# cytron-1.net
KiCad netlist of a schematic drawn in EAGLE
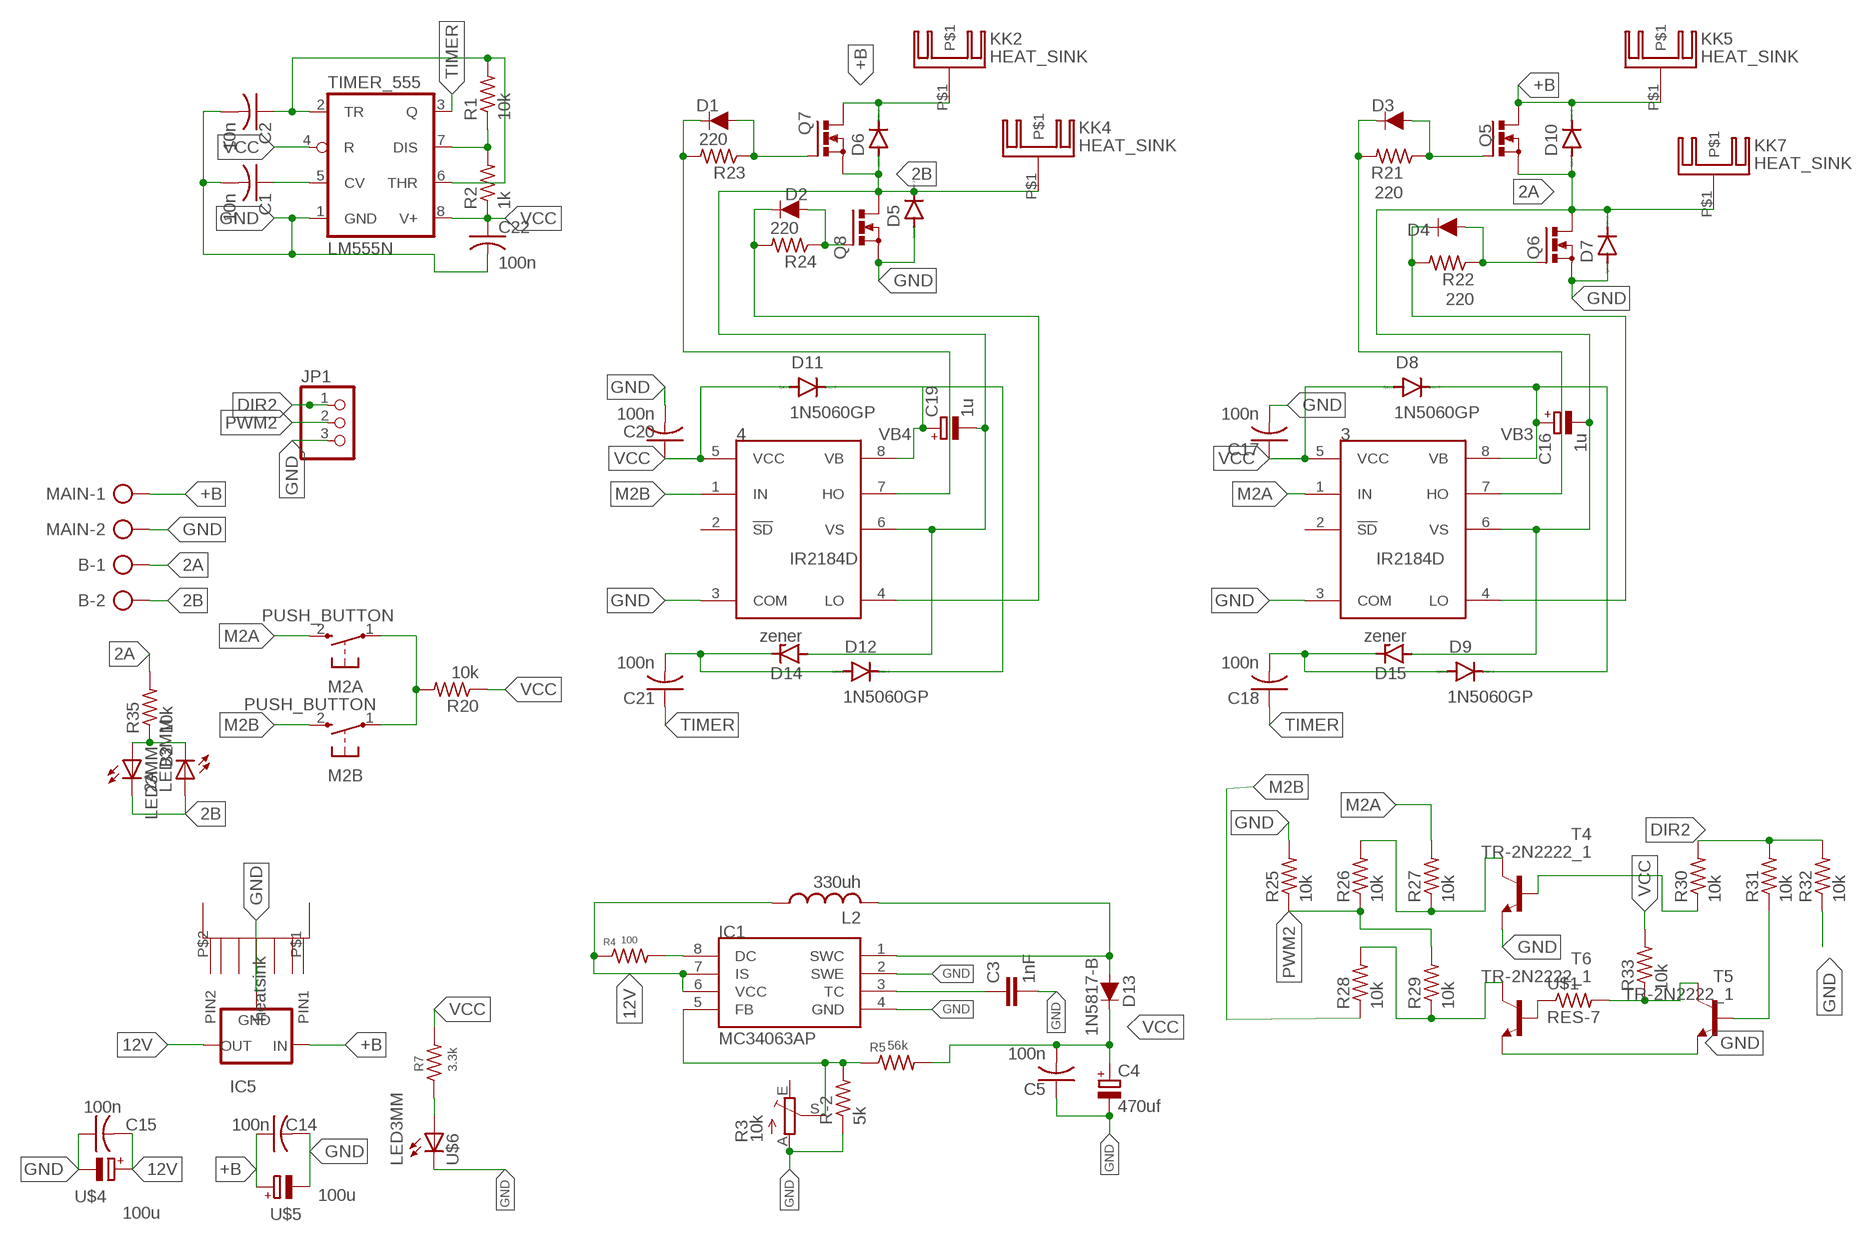
[diagram p0: schematic, sheet 1]

(export (version "E")
  (design (tool "Eeschema 10.0.6"))
  (components
    (comp (ref "2A")
      (value "LED3MM")
      (footprint "eagle-import:LED3MM")
      (libsource (lib "eagle-import") (part "LED3MM"))
    )
    (comp (ref "3")
      (value "IR2184D")
      (footprint "eagle-import:DIL08")
      (libsource (lib "eagle-import") (part "IR2184D"))
    )
    (comp (ref "4")
      (value "IR2184D")
      (footprint "eagle-import:DIL08")
      (libsource (lib "eagle-import") (part "IR2184D"))
    )
    (comp (ref "B")
      (value "ROSTA.POWER")
      (footprint "eagle-import:W239-302")
      (libsource (lib "eagle-import") (part "ROSTA.POWER"))
    )
    (comp (ref "B2")
      (value "LED3MM")
      (footprint "eagle-import:LED3MM")
      (libsource (lib "eagle-import") (part "LED3MM"))
    )
    (comp (ref "C1")
      (value "10n")
      (footprint "eagle-import:C025-025X050")
      (libsource (lib "eagle-import") (part "C-US025-025X050"))
    )
    (comp (ref "C2")
      (value "10n")
      (footprint "eagle-import:C025-025X050")
      (libsource (lib "eagle-import") (part "C-US025-025X050"))
    )
    (comp (ref "C3")
      (value "1nF")
      (footprint "eagle-import:C025-025X050")
      (fields (field (name "SPICEPREFIX") "C"))
      (libsource (lib "eagle-import") (part "CAPACITOR"))
    )
    (comp (ref "C4")
      (value "470uf")
      (footprint "eagle-import:E3,5-8")
      (fields (field (name "SPICEPREFIX") "C"))
      (libsource (lib "eagle-import") (part "CAP_POL"))
    )
    (comp (ref "C5")
      (value "100n")
      (footprint "eagle-import:C025-025X050")
      (libsource (lib "eagle-import") (part "C-US025-025X050"))
    )
    (comp (ref "C14")
      (value "100n")
      (footprint "eagle-import:C025-025X050")
      (libsource (lib "eagle-import") (part "C-US025-025X050"))
    )
    (comp (ref "C15")
      (value "100n")
      (footprint "eagle-import:C025-025X050")
      (libsource (lib "eagle-import") (part "C-US025-025X050"))
    )
    (comp (ref "C16")
      (value "1u")
      (footprint "eagle-import:E5-5")
      (libsource (lib "eagle-import") (part "CPOL-EUE5-5"))
    )
    (comp (ref "C17")
      (value "100n")
      (footprint "eagle-import:C025-025X050")
      (libsource (lib "eagle-import") (part "C-US025-025X050"))
    )
    (comp (ref "C18")
      (value "100n")
      (footprint "eagle-import:C025-025X050")
      (libsource (lib "eagle-import") (part "C-US025-025X050"))
    )
    (comp (ref "C19")
      (value "1u")
      (footprint "eagle-import:E5-5")
      (libsource (lib "eagle-import") (part "CPOL-EUE5-5"))
    )
    (comp (ref "C20")
      (value "100n")
      (footprint "eagle-import:C025-025X050")
      (libsource (lib "eagle-import") (part "C-US025-025X050"))
    )
    (comp (ref "C21")
      (value "100n")
      (footprint "eagle-import:C025-025X050")
      (libsource (lib "eagle-import") (part "C-US025-025X050"))
    )
    (comp (ref "C22")
      (value "100n")
      (footprint "eagle-import:C025-025X050")
      (libsource (lib "eagle-import") (part "C-US025-025X050"))
    )
    (comp (ref "D1")
      (value "1A/50V/1.1V")
      (footprint "eagle-import:DIODE-1N4001")
      (libsource (lib "eagle-import") (part "DIODE(1A)-PTH"))
    )
    (comp (ref "D2")
      (value "1A/50V/1.1V")
      (footprint "eagle-import:DIODE-1N4001")
      (libsource (lib "eagle-import") (part "DIODE(1A)-PTH"))
    )
    (comp (ref "D3")
      (value "1A/50V/1.1V")
      (footprint "eagle-import:DIODE-1N4001")
      (libsource (lib "eagle-import") (part "DIODE(1A)-PTH"))
    )
    (comp (ref "D4")
      (value "1A/50V/1.1V")
      (footprint "eagle-import:DIODE-1N4001")
      (libsource (lib "eagle-import") (part "DIODE(1A)-PTH"))
    )
    (comp (ref "D5")
      (value "BY396")
      (footprint "eagle-import:DO201-15")
      (libsource (lib "eagle-import") (part "BY396"))
    )
    (comp (ref "D6")
      (value "BY396")
      (footprint "eagle-import:DO201-15")
      (libsource (lib "eagle-import") (part "BY396"))
    )
    (comp (ref "D7")
      (value "BY396")
      (footprint "eagle-import:DO201-15")
      (libsource (lib "eagle-import") (part "BY396"))
    )
    (comp (ref "D8")
      (value "1N5060GP")
      (footprint "eagle-import:DO15-12")
      (libsource (lib "eagle-import") (part "1N5060GP"))
    )
    (comp (ref "D9")
      (value "1N5060GP")
      (footprint "eagle-import:DO15-12")
      (libsource (lib "eagle-import") (part "1N5060GP"))
    )
    (comp (ref "D10")
      (value "BY396")
      (footprint "eagle-import:DO201-15")
      (libsource (lib "eagle-import") (part "BY396"))
    )
    (comp (ref "D11")
      (value "1N5060GP")
      (footprint "eagle-import:DO15-12")
      (libsource (lib "eagle-import") (part "1N5060GP"))
    )
    (comp (ref "D12")
      (value "1N5060GP")
      (footprint "eagle-import:DO15-12")
      (libsource (lib "eagle-import") (part "1N5060GP"))
    )
    (comp (ref "D13")
      (value "1N5817-B")
      (footprint "eagle-import:DIODE-1N4001")
      (fields (field (name "SPICEPREFIX") "D"))
      (libsource (lib "eagle-import") (part "DIODE(1A)-PTH"))
    )
    (comp (ref "D14")
      (value "zener")
      (footprint "eagle-import:SOD81")
      (libsource (lib "eagle-import") (part "BZD23"))
    )
    (comp (ref "D15")
      (value "zener")
      (footprint "eagle-import:SOD81")
      (libsource (lib "eagle-import") (part "BZD23"))
    )
    (comp (ref "IC1")
      (value "MC34063AP")
      (footprint "eagle-import:DIL08")
      (fields (field (name "SPICEPREFIX") "X"))
      (libsource (lib "eagle-import") (part "MC34063AP"))
    )
    (comp (ref "IC5")
      (value "78XXS")
      (footprint "eagle-import:78XXS")
      (libsource (lib "eagle-import") (part "78XXS"))
    )
    (comp (ref "JP1")
      (value "PINHD-3_DATA")
      (footprint "eagle-import:1X03_DATA")
      (libsource (lib "eagle-import") (part "PINHD-3_DATA"))
    )
    (comp (ref "KK2")
      (value "HEAT_SINK")
      (footprint "eagle-import:SK95-2M3")
      (libsource (lib "eagle-import") (part "HEAT_SINK"))
    )
    (comp (ref "KK4")
      (value "HEAT_SINK")
      (footprint "eagle-import:SK95-2M3")
      (libsource (lib "eagle-import") (part "HEAT_SINK"))
    )
    (comp (ref "KK5")
      (value "HEAT_SINK")
      (footprint "eagle-import:SK95-2M3")
      (libsource (lib "eagle-import") (part "HEAT_SINK"))
    )
    (comp (ref "KK7")
      (value "HEAT_SINK")
      (footprint "eagle-import:SK95-2M3")
      (libsource (lib "eagle-import") (part "HEAT_SINK"))
    )
    (comp (ref "L2")
      (value "330uh")
      (footprint "eagle-import:POWER-CHOKE_WE-TPC")
      (libsource (lib "eagle-import") (part "L-USWE-TPC"))
    )
    (comp (ref "M2A")
      (value "PUSH_BUTTON")
      (footprint "eagle-import:B3F-10XX")
      (libsource (lib "eagle-import") (part "PUSH_BUTTON"))
    )
    (comp (ref "M2B")
      (value "PUSH_BUTTON")
      (footprint "eagle-import:B3F-10XX")
      (libsource (lib "eagle-import") (part "PUSH_BUTTON"))
    )
    (comp (ref "MAIN")
      (value "ROSTA.POWER")
      (footprint "eagle-import:W239-302")
      (libsource (lib "eagle-import") (part "ROSTA.POWER"))
    )
    (comp (ref "Q5")
      (value "MOSFET_NTO220BV")
      (footprint "eagle-import:TO220BV")
      (libsource (lib "eagle-import") (part "MOSFET_NTO220BV"))
    )
    (comp (ref "Q6")
      (value "MOSFET_NTO220BV")
      (footprint "eagle-import:TO220BV")
      (libsource (lib "eagle-import") (part "MOSFET_NTO220BV"))
    )
    (comp (ref "Q7")
      (value "MOSFET_NTO220BV")
      (footprint "eagle-import:TO220BV")
      (libsource (lib "eagle-import") (part "MOSFET_NTO220BV"))
    )
    (comp (ref "Q8")
      (value "MOSFET_NTO220BV")
      (footprint "eagle-import:TO220BV")
      (libsource (lib "eagle-import") (part "MOSFET_NTO220BV"))
    )
    (comp (ref "R-2")
      (value "5k")
      (footprint "eagle-import:0204_7")
      (libsource (lib "eagle-import") (part "RES-7"))
    )
    (comp (ref "R1")
      (value "10k")
      (footprint "eagle-import:0204_7")
      (libsource (lib "eagle-import") (part "R-US_0204/7"))
    )
    (comp (ref "R2")
      (value "1k")
      (footprint "eagle-import:0204_7")
      (libsource (lib "eagle-import") (part "R-US_0204/7"))
    )
    (comp (ref "R3")
      (value "10k")
      (footprint "eagle-import:CA6V")
      (fields (field (name "SPICEPREFIX") "J"))
      (libsource (lib "eagle-import") (part "TRIM_EU-CA6V"))
    )
    (comp (ref "R4")
      (value "100")
      (footprint "eagle-import:0204_7")
      (fields (field (name "SPICEPREFIX") "R"))
      (libsource (lib "eagle-import") (part "RES-7"))
    )
    (comp (ref "R5")
      (value "56k")
      (footprint "eagle-import:0204_7")
      (fields (field (name "SPICEPREFIX") "R"))
      (libsource (lib "eagle-import") (part "RES-7"))
    )
    (comp (ref "R7")
      (value "3.3k")
      (footprint "eagle-import:0204_7")
      (fields (field (name "SPICEPREFIX") "R"))
      (libsource (lib "eagle-import") (part "RES-7"))
    )
    (comp (ref "R20")
      (value "10k")
      (footprint "eagle-import:0204_7")
      (libsource (lib "eagle-import") (part "R-US_0204/7"))
    )
    (comp (ref "R21")
      (value "220")
      (footprint "eagle-import:0204_7")
      (libsource (lib "eagle-import") (part "R-US_0204/7"))
    )
    (comp (ref "R22")
      (value "220")
      (footprint "eagle-import:0204_7")
      (libsource (lib "eagle-import") (part "R-US_0204/7"))
    )
    (comp (ref "R23")
      (value "220")
      (footprint "eagle-import:0204_7")
      (libsource (lib "eagle-import") (part "R-US_0204/7"))
    )
    (comp (ref "R24")
      (value "220")
      (footprint "eagle-import:0204_7")
      (libsource (lib "eagle-import") (part "R-US_0204/7"))
    )
    (comp (ref "R25")
      (value "10k")
      (footprint "eagle-import:0204_7")
      (libsource (lib "eagle-import") (part "R-US_0204/7"))
    )
    (comp (ref "R26")
      (value "10k")
      (footprint "eagle-import:0204_7")
      (libsource (lib "eagle-import") (part "R-US_0204/7"))
    )
    (comp (ref "R27")
      (value "10k")
      (footprint "eagle-import:0204_7")
      (libsource (lib "eagle-import") (part "R-US_0204/7"))
    )
    (comp (ref "R28")
      (value "10k")
      (footprint "eagle-import:0204_7")
      (libsource (lib "eagle-import") (part "R-US_0204/7"))
    )
    (comp (ref "R29")
      (value "10k")
      (footprint "eagle-import:0204_7")
      (libsource (lib "eagle-import") (part "R-US_0204/7"))
    )
    (comp (ref "R30")
      (value "10k")
      (footprint "eagle-import:0204_7")
      (libsource (lib "eagle-import") (part "R-US_0204/7"))
    )
    (comp (ref "R31")
      (value "10k")
      (footprint "eagle-import:0204_7")
      (libsource (lib "eagle-import") (part "R-US_0204/7"))
    )
    (comp (ref "R32")
      (value "10k")
      (footprint "eagle-import:0204_7")
      (libsource (lib "eagle-import") (part "R-US_0204/7"))
    )
    (comp (ref "R33")
      (value "10k")
      (footprint "eagle-import:0204_7")
      (libsource (lib "eagle-import") (part "R-US_0204/7"))
    )
    (comp (ref "R35")
      (value "10k")
      (footprint "eagle-import:0204_7")
      (libsource (lib "eagle-import") (part "R-US_0204/7"))
    )
    (comp (ref "T4")
      (value "TR-2N2222_1")
      (footprint "eagle-import:TO92-EBC")
      (fields (field (name "SPICEPREFIX") "J"))
      (libsource (lib "eagle-import") (part "TR-2N2222_1"))
    )
    (comp (ref "T5")
      (value "TR-2N2222_1")
      (footprint "eagle-import:TO92-EBC")
      (fields (field (name "SPICEPREFIX") "J"))
      (libsource (lib "eagle-import") (part "TR-2N2222_1"))
    )
    (comp (ref "T6")
      (value "TR-2N2222_1")
      (footprint "eagle-import:TO92-EBC")
      (fields (field (name "SPICEPREFIX") "J"))
      (libsource (lib "eagle-import") (part "TR-2N2222_1"))
    )
    (comp (ref "TIMER_555")
      (value "LM555N")
      (footprint "eagle-import:DIL08")
      (libsource (lib "eagle-import") (part "555NLM"))
    )
    (comp (ref "U$1")
      (value "RES-7")
      (footprint "eagle-import:0204_7")
      (fields (field (name "SPICEPREFIX") "B"))
      (libsource (lib "eagle-import") (part "RES-7"))
    )
    (comp (ref "U$3")
      (value "HEAT-SINK")
      (footprint "eagle-import:HEAT_SINK")
      (libsource (lib "eagle-import") (part "HEAT-SINK"))
    )
    (comp (ref "U$4")
      (value "100u")
      (footprint "eagle-import:E3,5-8")
      (libsource (lib "eagle-import") (part "CAP_POL"))
    )
    (comp (ref "U$5")
      (value "100u")
      (footprint "eagle-import:E3,5-8")
      (libsource (lib "eagle-import") (part "CAP_POL"))
    )
    (comp (ref "U$6")
      (value "LED3MM")
      (footprint "eagle-import:LED3MM")
      (fields (field (name "SPICEPREFIX") "B"))
      (libsource (lib "eagle-import") (part "LED3MM"))
    )
  )
  (nets
    (net (code "1") (name "+B") (class "Default")
      (node (ref "C14") (pin "1") (pinfunction "1_1") (pintype "passive"))
      (node (ref "D10") (pin "C") (pinfunction "C_C") (pintype "passive"))
      (node (ref "D6") (pin "C") (pinfunction "C_C") (pintype "passive"))
      (node (ref "IC5") (pin "IN") (pinfunction "IN_IN") (pintype "input"))
      (node (ref "KK2") (pin "P$1") (pinfunction "P$1_P$1") (pintype "bidirectional"))
      (node (ref "KK5") (pin "P$1") (pinfunction "P$1_P$1") (pintype "bidirectional"))
      (node (ref "MAIN") (pin "1") (pinfunction "KL_1") (pintype "passive"))
      (node (ref "Q5") (pin "D") (pinfunction "D_D") (pintype "passive"))
      (node (ref "Q7") (pin "D") (pinfunction "D_D") (pintype "passive"))
      (node (ref "U$5") (pin "+") (pinfunction "+_+") (pintype "passive"))
    )
    (net (code "2") (name "/VB3") (class "Default")
      (node (ref "3") (pin "8") (pinfunction "VB_8") (pintype "power_in"))
      (node (ref "C16") (pin "+") (pinfunction "+_+") (pintype "passive"))
      (node (ref "D8") (pin "C") (pinfunction "C_C") (pintype "passive"))
      (node (ref "D9") (pin "C") (pinfunction "C_C") (pintype "passive"))
    )
    (net (code "3") (name "/VB4") (class "Default")
      (node (ref "4") (pin "8") (pinfunction "VB_8") (pintype "power_in"))
      (node (ref "C19") (pin "+") (pinfunction "+_+") (pintype "passive"))
      (node (ref "D11") (pin "C") (pinfunction "C_C") (pintype "passive"))
      (node (ref "D12") (pin "C") (pinfunction "C_C") (pintype "passive"))
    )
    (net (code "4") (name "2A") (class "Default")
      (node (ref "3") (pin "6") (pinfunction "VS_6") (pintype "power_in"))
      (node (ref "B") (pin "1") (pinfunction "KL_1") (pintype "passive"))
      (node (ref "C16") (pin "-") (pinfunction "-_-") (pintype "passive"))
      (node (ref "D10") (pin "A") (pinfunction "A_A") (pintype "passive"))
      (node (ref "D15") (pin "A") (pinfunction "A_A") (pintype "passive"))
      (node (ref "D7") (pin "C") (pinfunction "C_C") (pintype "passive"))
      (node (ref "KK7") (pin "P$1") (pinfunction "P$1_P$1") (pintype "bidirectional"))
      (node (ref "Q5") (pin "S") (pinfunction "S_S") (pintype "passive"))
      (node (ref "Q6") (pin "D") (pinfunction "D_D") (pintype "passive"))
      (node (ref "R35") (pin "2") (pinfunction "2_2") (pintype "passive"))
    )
    (net (code "5") (name "2B") (class "Default")
      (node (ref "2A") (pin "K") (pinfunction "C_K") (pintype "passive"))
      (node (ref "4") (pin "6") (pinfunction "VS_6") (pintype "power_in"))
      (node (ref "B") (pin "2") (pinfunction "KL_2") (pintype "passive"))
      (node (ref "B2") (pin "A") (pinfunction "A_A") (pintype "passive"))
      (node (ref "C19") (pin "-") (pinfunction "-_-") (pintype "passive"))
      (node (ref "D14") (pin "A") (pinfunction "A_A") (pintype "passive"))
      (node (ref "D5") (pin "C") (pinfunction "C_C") (pintype "passive"))
      (node (ref "D6") (pin "A") (pinfunction "A_A") (pintype "passive"))
      (node (ref "KK4") (pin "P$1") (pinfunction "P$1_P$1") (pintype "bidirectional"))
      (node (ref "Q7") (pin "S") (pinfunction "S_S") (pintype "passive"))
      (node (ref "Q8") (pin "D") (pinfunction "D_D") (pintype "passive"))
    )
    (net (code "6") (name "12V") (class "Default")
      (node (ref "C15") (pin "2") (pinfunction "2_2") (pintype "passive"))
      (node (ref "IC1") (pin "6") (pinfunction "VCC_6") (pintype "passive"))
      (node (ref "IC1") (pin "7") (pinfunction "IS_7") (pintype "passive"))
      (node (ref "IC5") (pin "OUT") (pinfunction "OUT_OUT") (pintype "passive"))
      (node (ref "L2") (pin "1") (pinfunction "1_1") (pintype "passive"))
      (node (ref "R4") (pin "1") (pinfunction "1_1") (pintype "passive"))
      (node (ref "U$4") (pin "+") (pinfunction "+_+") (pintype "passive"))
    )
    (net (code "7") (name "DIR2") (class "Default")
      (node (ref "JP1") (pin "1") (pinfunction "1_1") (pintype "passive"))
      (node (ref "R30") (pin "2") (pinfunction "2_2") (pintype "passive"))
      (node (ref "R31") (pin "2") (pinfunction "2_2") (pintype "passive"))
      (node (ref "R32") (pin "2") (pinfunction "2_2") (pintype "passive"))
    )
    (net (code "8") (name "GND") (class "Default")
      (node (ref "3") (pin "3") (pinfunction "COM_3") (pintype "power_in"))
      (node (ref "4") (pin "3") (pinfunction "COM_3") (pintype "power_in"))
      (node (ref "C1") (pin "2") (pinfunction "2_2") (pintype "passive"))
      (node (ref "C14") (pin "2") (pinfunction "2_2") (pintype "passive"))
      (node (ref "C15") (pin "1") (pinfunction "1_1") (pintype "passive"))
      (node (ref "C17") (pin "2") (pinfunction "2_2") (pintype "passive"))
      (node (ref "C2") (pin "2") (pinfunction "2_2") (pintype "passive"))
      (node (ref "C20") (pin "2") (pinfunction "2_2") (pintype "passive"))
      (node (ref "C22") (pin "2") (pinfunction "2_2") (pintype "passive"))
      (node (ref "C3") (pin "2") (pinfunction "2_2") (pintype "passive"))
      (node (ref "C4") (pin "-") (pinfunction "-_-") (pintype "passive"))
      (node (ref "C5") (pin "1") (pinfunction "1_1") (pintype "passive"))
      (node (ref "D5") (pin "A") (pinfunction "A_A") (pintype "passive"))
      (node (ref "D7") (pin "A") (pinfunction "A_A") (pintype "passive"))
      (node (ref "IC1") (pin "2") (pinfunction "SWE_2") (pintype "passive"))
      (node (ref "IC1") (pin "4") (pinfunction "GND_4") (pintype "passive"))
      (node (ref "IC5") (pin "GND") (pinfunction "GND_GND") (pintype "input"))
      (node (ref "JP1") (pin "3") (pinfunction "3_3") (pintype "passive"))
      (node (ref "MAIN") (pin "2") (pinfunction "KL_2") (pintype "passive"))
      (node (ref "Q6") (pin "S") (pinfunction "S_S") (pintype "passive"))
      (node (ref "Q8") (pin "S") (pinfunction "S_S") (pintype "passive"))
      (node (ref "R-2") (pin "1") (pinfunction "1_1") (pintype "passive"))
      (node (ref "R25") (pin "2") (pinfunction "2_2") (pintype "passive"))
      (node (ref "R3") (pin "A") (pinfunction "A_A") (pintype "passive"))
      (node (ref "R32") (pin "1") (pinfunction "1_1") (pintype "passive"))
      (node (ref "T4") (pin "E") (pinfunction "E_E") (pintype "passive"))
      (node (ref "T5") (pin "E") (pinfunction "E_E") (pintype "passive"))
      (node (ref "T6") (pin "E") (pinfunction "E_E") (pintype "passive"))
      (node (ref "TIMER_555") (pin "1") (pinfunction "GND_1") (pintype "power_in"))
      (node (ref "U$4") (pin "-") (pinfunction "-_-") (pintype "passive"))
      (node (ref "U$5") (pin "-") (pinfunction "-_-") (pintype "passive"))
      (node (ref "U$6") (pin "K") (pinfunction "C_K") (pintype "passive"))
    )
    (net (code "9") (name "M2A") (class "Default")
      (node (ref "3") (pin "1") (pinfunction "IN_1") (pintype "input"))
      (node (ref "M2A") (pin "2") (pinfunction "S_2") (pintype "passive"))
      (node (ref "R27") (pin "2") (pinfunction "2_2") (pintype "passive"))
    )
    (net (code "10") (name "M2B") (class "Default")
      (node (ref "4") (pin "1") (pinfunction "IN_1") (pintype "input"))
      (node (ref "M2B") (pin "2") (pinfunction "S_2") (pintype "passive"))
      (node (ref "R28") (pin "1") (pinfunction "1_1") (pintype "passive"))
    )
    (net (code "11") (name "Net-(3-HO)") (class "Default")
      (node (ref "3") (pin "7") (pinfunction "HO_7") (pintype "output"))
      (node (ref "D3") (pin "C") (pinfunction "C_C") (pintype "passive"))
      (node (ref "R21") (pin "2") (pinfunction "2_2") (pintype "passive"))
    )
    (net (code "12") (name "Net-(3-LO)") (class "Default")
      (node (ref "3") (pin "4") (pinfunction "LO_4") (pintype "output"))
      (node (ref "D4") (pin "C") (pinfunction "C_C") (pintype "passive"))
      (node (ref "R22") (pin "2") (pinfunction "2_2") (pintype "passive"))
    )
    (net (code "13") (name "Net-(4-HO)") (class "Default")
      (node (ref "4") (pin "7") (pinfunction "HO_7") (pintype "output"))
      (node (ref "D1") (pin "C") (pinfunction "C_C") (pintype "passive"))
      (node (ref "R23") (pin "2") (pinfunction "2_2") (pintype "passive"))
    )
    (net (code "14") (name "Net-(4-LO)") (class "Default")
      (node (ref "4") (pin "4") (pinfunction "LO_4") (pintype "output"))
      (node (ref "D2") (pin "C") (pinfunction "C_C") (pintype "passive"))
      (node (ref "R24") (pin "2") (pinfunction "2_2") (pintype "passive"))
    )
    (net (code "15") (name "Net-(B2-C)") (class "Default")
      (node (ref "2A") (pin "A") (pinfunction "A_A") (pintype "passive"))
      (node (ref "B2") (pin "K") (pinfunction "C_K") (pintype "passive"))
      (node (ref "R35") (pin "1") (pinfunction "1_1") (pintype "passive"))
    )
    (net (code "16") (name "Net-(C18-Pad2)") (class "Default")
      (node (ref "C18") (pin "2") (pinfunction "2_2") (pintype "passive"))
      (node (ref "D15") (pin "C") (pinfunction "C_C") (pintype "passive"))
      (node (ref "D9") (pin "A") (pinfunction "A_A") (pintype "passive"))
    )
    (net (code "17") (name "Net-(C21-Pad2)") (class "Default")
      (node (ref "C21") (pin "2") (pinfunction "2_2") (pintype "passive"))
      (node (ref "D12") (pin "A") (pinfunction "A_A") (pintype "passive"))
      (node (ref "D14") (pin "C") (pinfunction "C_C") (pintype "passive"))
    )
    (net (code "18") (name "Net-(D1-PadA)") (class "Default")
      (node (ref "D1") (pin "A") (pinfunction "A_A") (pintype "passive"))
      (node (ref "Q7") (pin "G") (pinfunction "G_G") (pintype "passive"))
      (node (ref "R23") (pin "1") (pinfunction "1_1") (pintype "passive"))
    )
    (net (code "19") (name "Net-(D2-PadA)") (class "Default")
      (node (ref "D2") (pin "A") (pinfunction "A_A") (pintype "passive"))
      (node (ref "Q8") (pin "G") (pinfunction "G_G") (pintype "passive"))
      (node (ref "R24") (pin "1") (pinfunction "1_1") (pintype "passive"))
    )
    (net (code "20") (name "Net-(D3-PadA)") (class "Default")
      (node (ref "D3") (pin "A") (pinfunction "A_A") (pintype "passive"))
      (node (ref "Q5") (pin "G") (pinfunction "G_G") (pintype "passive"))
      (node (ref "R21") (pin "1") (pinfunction "1_1") (pintype "passive"))
    )
    (net (code "21") (name "Net-(D4-PadA)") (class "Default")
      (node (ref "D4") (pin "A") (pinfunction "A_A") (pintype "passive"))
      (node (ref "Q6") (pin "G") (pinfunction "G_G") (pintype "passive"))
      (node (ref "R22") (pin "1") (pinfunction "1_1") (pintype "passive"))
    )
    (net (code "22") (name "Net-(IC1-DC)") (class "Default")
      (node (ref "IC1") (pin "8") (pinfunction "DC_8") (pintype "passive"))
      (node (ref "R4") (pin "2") (pinfunction "2_2") (pintype "passive"))
    )
    (net (code "23") (name "Net-(IC1-FB)") (class "Default")
      (node (ref "IC1") (pin "5") (pinfunction "FB_5") (pintype "passive"))
      (node (ref "R-2") (pin "2") (pinfunction "2_2") (pintype "passive"))
      (node (ref "R3") (pin "S") (pinfunction "S_S") (pintype "passive"))
      (node (ref "R5") (pin "1") (pinfunction "1_1") (pintype "passive"))
    )
    (net (code "24") (name "Net-(IC1-SWC)") (class "Default")
      (node (ref "D13") (pin "A") (pinfunction "A_A") (pintype "passive"))
      (node (ref "IC1") (pin "1") (pinfunction "SWC_1") (pintype "passive"))
      (node (ref "L2") (pin "2") (pinfunction "2_2") (pintype "passive"))
    )
    (net (code "25") (name "Net-(IC1-TC)") (class "Default")
      (node (ref "C3") (pin "1") (pinfunction "1_1") (pintype "passive"))
      (node (ref "IC1") (pin "3") (pinfunction "TC_3") (pintype "passive"))
    )
    (net (code "26") (name "Net-(M2A-P)") (class "Default")
      (node (ref "M2A") (pin "1") (pinfunction "P_1") (pintype "passive"))
      (node (ref "M2B") (pin "1") (pinfunction "P_1") (pintype "passive"))
      (node (ref "R20") (pin "2") (pinfunction "2_2") (pintype "passive"))
    )
    (net (code "27") (name "Net-(R7-Pad1)") (class "Default")
      (node (ref "R7") (pin "1") (pinfunction "1_1") (pintype "passive"))
      (node (ref "U$6") (pin "A") (pinfunction "A_A") (pintype "passive"))
    )
    (net (code "28") (name "Net-(R26-Pad2)") (class "Default")
      (node (ref "R26") (pin "2") (pinfunction "2_2") (pintype "passive"))
      (node (ref "R27") (pin "1") (pinfunction "1_1") (pintype "passive"))
      (node (ref "T4") (pin "C") (pinfunction "C_C") (pintype "passive"))
    )
    (net (code "29") (name "Net-(R28-Pad2)") (class "Default")
      (node (ref "R28") (pin "2") (pinfunction "2_2") (pintype "passive"))
      (node (ref "R29") (pin "1") (pinfunction "1_1") (pintype "passive"))
      (node (ref "T6") (pin "C") (pinfunction "C_C") (pintype "passive"))
    )
    (net (code "30") (name "Net-(R30-Pad1)") (class "Default")
      (node (ref "R30") (pin "1") (pinfunction "1_1") (pintype "passive"))
      (node (ref "T4") (pin "B") (pinfunction "B_B") (pintype "passive"))
    )
    (net (code "31") (name "Net-(R31-Pad1)") (class "Default")
      (node (ref "R31") (pin "1") (pinfunction "1_1") (pintype "passive"))
      (node (ref "T5") (pin "B") (pinfunction "B_B") (pintype "passive"))
    )
    (net (code "32") (name "Net-(R33-Pad1)") (class "Default")
      (node (ref "R33") (pin "1") (pinfunction "1_1") (pintype "passive"))
      (node (ref "T5") (pin "C") (pinfunction "C_C") (pintype "passive"))
      (node (ref "U$1") (pin "2") (pinfunction "2_2") (pintype "passive"))
    )
    (net (code "33") (name "Net-(T6-PadB)") (class "Default")
      (node (ref "T6") (pin "B") (pinfunction "B_B") (pintype "passive"))
      (node (ref "U$1") (pin "1") (pinfunction "1_1") (pintype "passive"))
    )
    (net (code "34") (name "Net-(TIMER_555-CV)") (class "Default")
      (node (ref "C1") (pin "1") (pinfunction "1_1") (pintype "passive"))
      (node (ref "TIMER_555") (pin "5") (pinfunction "CV_5") (pintype "input"))
    )
    (net (code "35") (name "Net-(TIMER_555-DIS)") (class "Default")
      (node (ref "R1") (pin "1") (pinfunction "1_1") (pintype "passive"))
      (node (ref "R2") (pin "2") (pinfunction "2_2") (pintype "passive"))
      (node (ref "TIMER_555") (pin "7") (pinfunction "DIS_7") (pintype "input"))
    )
    (net (code "36") (name "Net-(TIMER_555-THR)") (class "Default")
      (node (ref "C2") (pin "1") (pinfunction "1_1") (pintype "passive"))
      (node (ref "R1") (pin "2") (pinfunction "2_2") (pintype "passive"))
      (node (ref "TIMER_555") (pin "2") (pinfunction "TR_2") (pintype "input"))
      (node (ref "TIMER_555") (pin "6") (pinfunction "THR_6") (pintype "input"))
    )
    (net (code "37") (name "PWM2") (class "Default")
      (node (ref "JP1") (pin "2") (pinfunction "2_2") (pintype "passive"))
      (node (ref "R25") (pin "1") (pinfunction "1_1") (pintype "passive"))
      (node (ref "R26") (pin "1") (pinfunction "1_1") (pintype "passive"))
      (node (ref "R29") (pin "2") (pinfunction "2_2") (pintype "passive"))
    )
    (net (code "38") (name "TIMER") (class "Default")
      (node (ref "C18") (pin "1") (pinfunction "1_1") (pintype "passive"))
      (node (ref "C21") (pin "1") (pinfunction "1_1") (pintype "passive"))
      (node (ref "TIMER_555") (pin "3") (pinfunction "Q_3") (pintype "output"))
    )
    (net (code "39") (name "VCC") (class "Default")
      (node (ref "3") (pin "5") (pinfunction "VCC_5") (pintype "power_in"))
      (node (ref "4") (pin "5") (pinfunction "VCC_5") (pintype "power_in"))
      (node (ref "C17") (pin "1") (pinfunction "1_1") (pintype "passive"))
      (node (ref "C20") (pin "1") (pinfunction "1_1") (pintype "passive"))
      (node (ref "C22") (pin "1") (pinfunction "1_1") (pintype "passive"))
      (node (ref "C4") (pin "+") (pinfunction "+_+") (pintype "passive"))
      (node (ref "C5") (pin "2") (pinfunction "2_2") (pintype "passive"))
      (node (ref "D11") (pin "A") (pinfunction "A_A") (pintype "passive"))
      (node (ref "D13") (pin "C") (pinfunction "C_C") (pintype "passive"))
      (node (ref "D8") (pin "A") (pinfunction "A_A") (pintype "passive"))
      (node (ref "R2") (pin "1") (pinfunction "1_1") (pintype "passive"))
      (node (ref "R20") (pin "1") (pinfunction "1_1") (pintype "passive"))
      (node (ref "R33") (pin "2") (pinfunction "2_2") (pintype "passive"))
      (node (ref "R5") (pin "2") (pinfunction "2_2") (pintype "passive"))
      (node (ref "R7") (pin "2") (pinfunction "2_2") (pintype "passive"))
      (node (ref "TIMER_555") (pin "4") (pinfunction "R_4") (pintype "input"))
      (node (ref "TIMER_555") (pin "8") (pinfunction "V+_8") (pintype "power_in"))
    )
    (net (code "40") (name "unconnected-(3-~{SD}-Pad2)") (class "Default")
      (node (ref "3") (pin "2") (pinfunction "~{SD}_2") (pintype "input"))
    )
    (net (code "41") (name "unconnected-(4-~{SD}-Pad2)") (class "Default")
      (node (ref "4") (pin "2") (pinfunction "~{SD}_2") (pintype "input"))
    )
    (net (code "42") (name "unconnected-(R3-PadE)") (class "Default")
      (node (ref "R3") (pin "E") (pinfunction "E_E") (pintype "passive"))
    )
    (net (code "43") (name "unconnected-(U$3-PIN1-PadP$1)") (class "Default")
      (node (ref "U$3") (pin "P$1") (pinfunction "PIN1_P$1") (pintype "bidirectional"))
    )
    (net (code "44") (name "unconnected-(U$3-PIN2-PadP$2)") (class "Default")
      (node (ref "U$3") (pin "P$2") (pinfunction "PIN2_P$2") (pintype "bidirectional"))
    )
  )
)
